# GSM_GPS.net
KiCad netlist of a schematic drawn in EAGLE
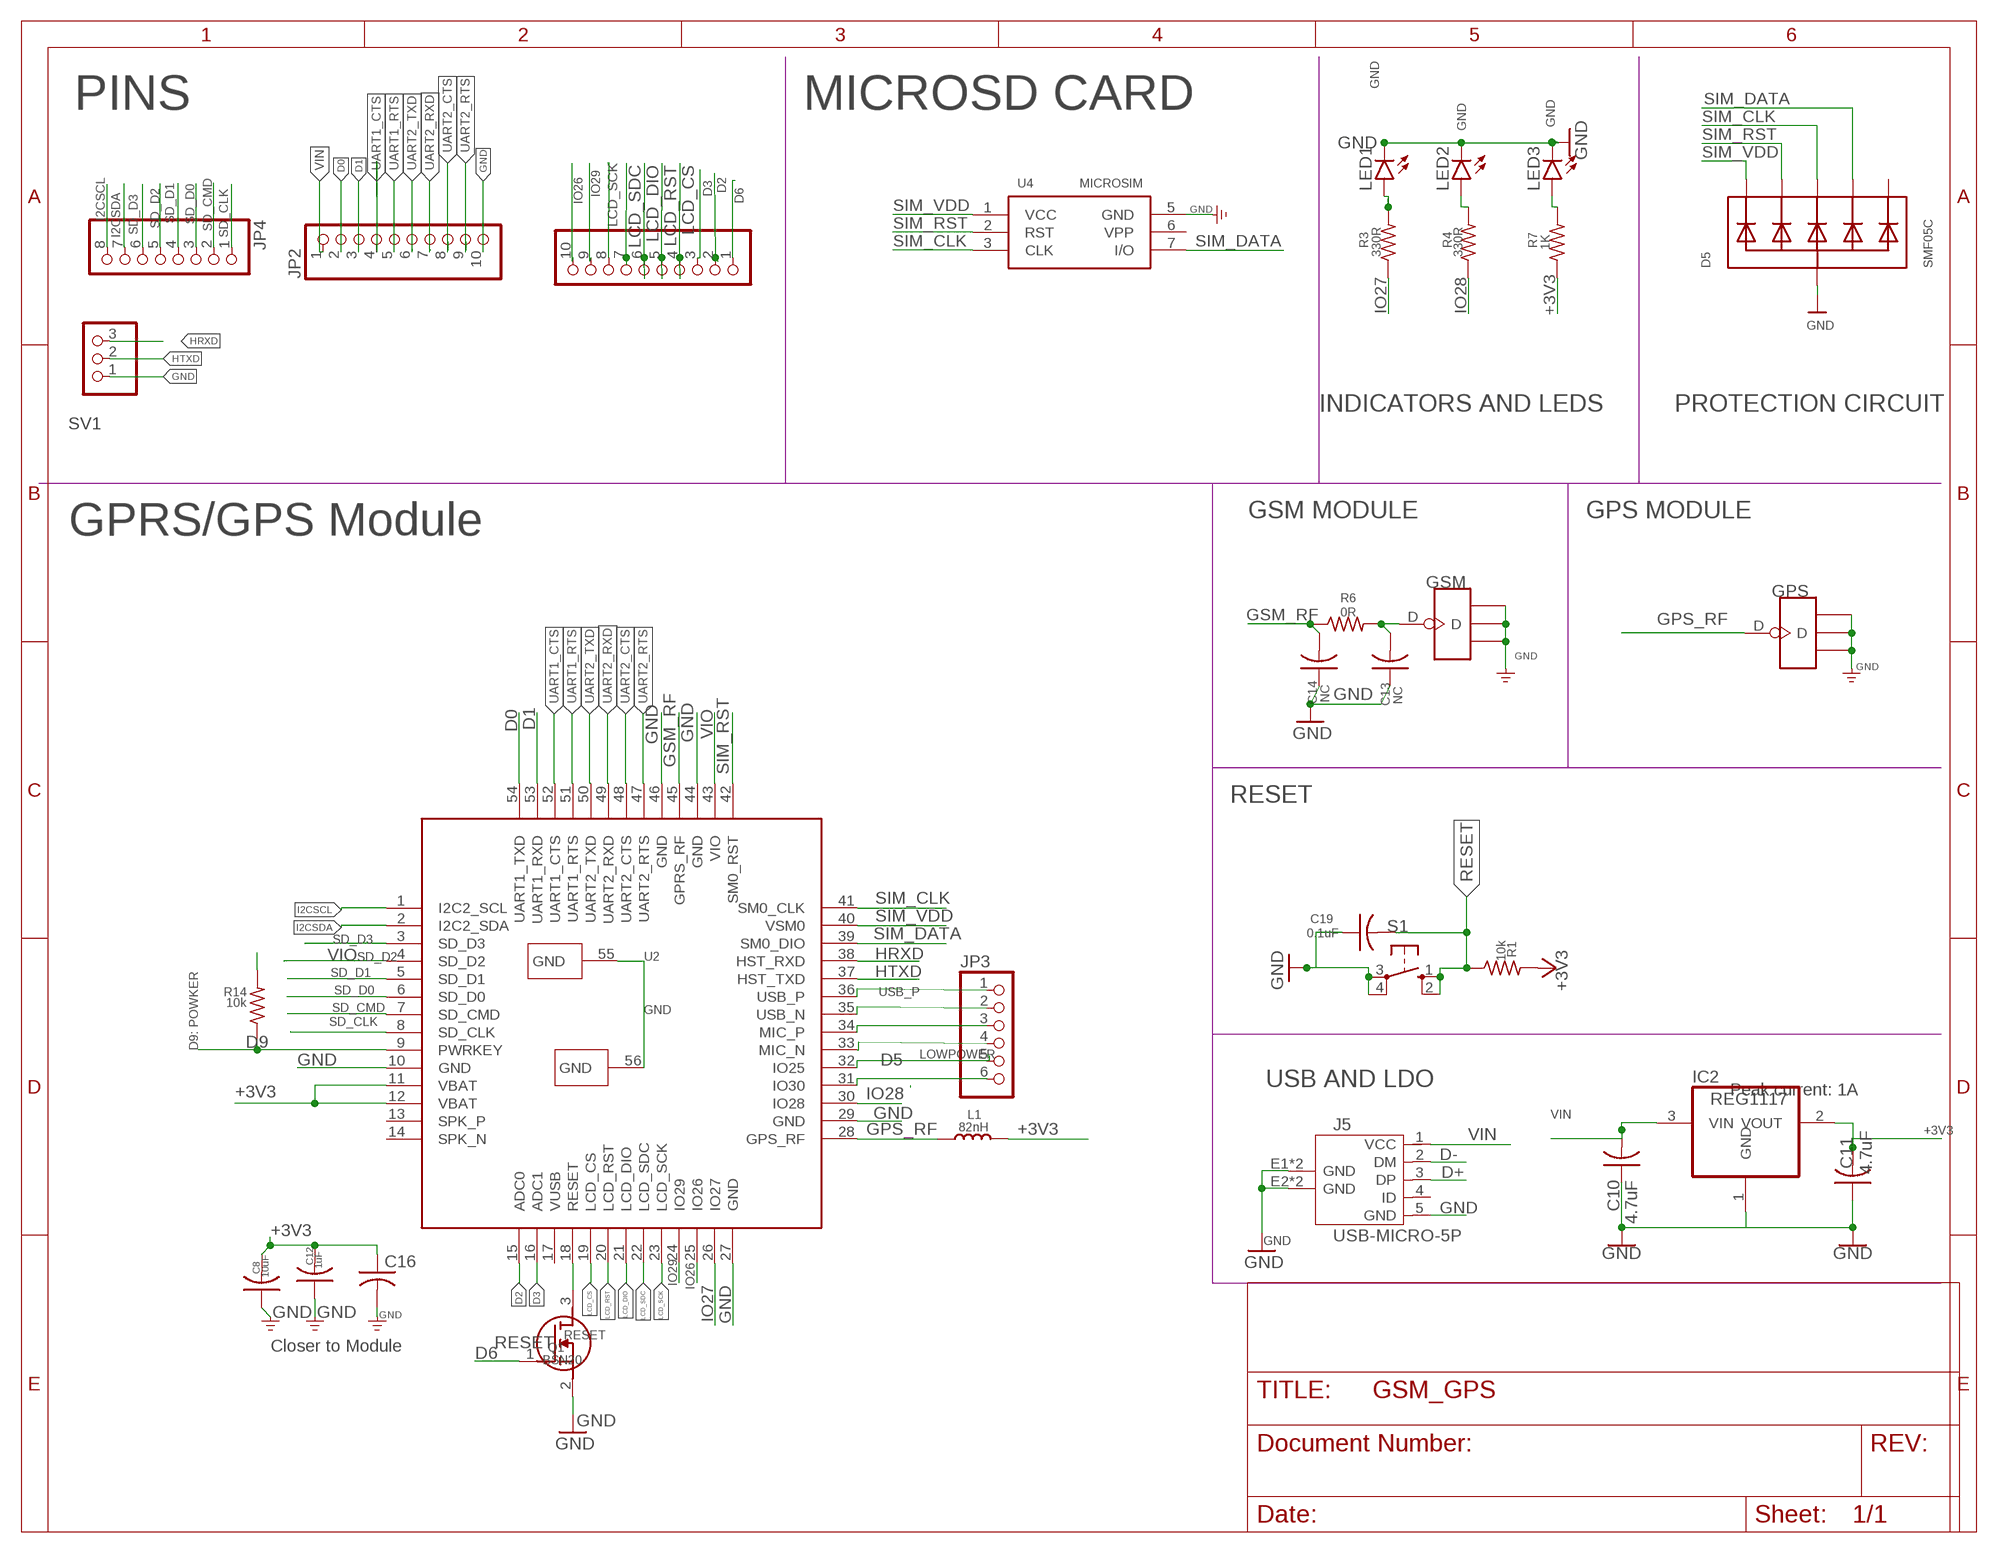
[diagram p0: schematic, sheet 1]

(export (version "E")
  (design (tool "Eeschema 10.0.6"))
  (components
    (comp (ref "C8")
      (value "10uF")
      (footprint "eagle-import:C0805")
      (libsource (lib "eagle-import") (part "C-USC0805"))
    )
    (comp (ref "C10")
      (value "4.7uF")
      (footprint "eagle-import:C0805")
      (libsource (lib "eagle-import") (part "C-USC0805"))
    )
    (comp (ref "C11")
      (value "4.7uF")
      (footprint "eagle-import:C0805")
      (libsource (lib "eagle-import") (part "C-USC0805"))
    )
    (comp (ref "C12")
      (value "1uF")
      (footprint "eagle-import:C0805")
      (libsource (lib "eagle-import") (part "C-USC0805"))
    )
    (comp (ref "C13")
      (value "NC")
      (footprint "eagle-import:C0805")
      (libsource (lib "eagle-import") (part "C-USC0805"))
    )
    (comp (ref "C14")
      (value "NC")
      (footprint "eagle-import:C0805")
      (libsource (lib "eagle-import") (part "C-USC0805"))
    )
    (comp (ref "C16")
      (value "100uF")
      (footprint "eagle-import:C0805")
      (libsource (lib "eagle-import") (part "C-USC0805"))
    )
    (comp (ref "C19")
      (value "0.1uF")
      (footprint "eagle-import:C0805")
      (libsource (lib "eagle-import") (part "C-USC0805"))
    )
    (comp (ref "D5")
      (value "SMF05C")
      (footprint "eagle-import:SOT363")
      (libsource (lib "eagle-import") (part "TVSARRAY_5LANE"))
    )
    (comp (ref "GPS")
      (value "ANTENNA-U-FL")
      (footprint "eagle-import:4P-U-FL")
      (libsource (lib "eagle-import") (part "ANTENNA-U-FL"))
    )
    (comp (ref "GSM")
      (value "ANTENNA-U-FL")
      (footprint "eagle-import:4P-U-FL")
      (libsource (lib "eagle-import") (part "ANTENNA-U-FL"))
    )
    (comp (ref "IC2")
      (value "REG1117")
      (footprint "eagle-import:SOT223")
      (libsource (lib "eagle-import") (part "REG1117"))
    )
    (comp (ref "J2")
      (value "PINHD-1X10")
      (footprint "eagle-import:1X10")
      (libsource (lib "eagle-import") (part "PINHD-1X10"))
    )
    (comp (ref "J5")
      (value "USB-MICRO-5P")
      (footprint "eagle-import:MICRO-USB-5P")
      (libsource (lib "eagle-import") (part "USB-MICRO-5P"))
    )
    (comp (ref "JP2")
      (value "PINHD-1X10")
      (footprint "eagle-import:1X10")
      (libsource (lib "eagle-import") (part "PINHD-1X10"))
    )
    (comp (ref "JP3")
      (value "PINHD-1X6")
      (footprint "eagle-import:1X06")
      (libsource (lib "eagle-import") (part "PINHD-1X6"))
    )
    (comp (ref "JP4")
      (value "PINHD-1X8")
      (footprint "eagle-import:1X08")
      (libsource (lib "eagle-import") (part "PINHD-1X8"))
    )
    (comp (ref "L1")
      (value "82nH")
      (footprint "eagle-import:L0603")
      (libsource (lib "eagle-import") (part "L'0603'"))
    )
    (comp (ref "LED1")
      (value "LEDCHIPLED_0805")
      (footprint "eagle-import:CHIPLED_0805")
      (libsource (lib "eagle-import") (part "LEDCHIPLED_0805"))
    )
    (comp (ref "LED2")
      (value "LEDCHIPLED_0805")
      (footprint "eagle-import:CHIPLED_0805")
      (libsource (lib "eagle-import") (part "LEDCHIPLED_0805"))
    )
    (comp (ref "LED3")
      (value "LEDCHIPLED_0805")
      (footprint "eagle-import:CHIPLED_0805")
      (libsource (lib "eagle-import") (part "LEDCHIPLED_0805"))
    )
    (comp (ref "Q1")
      (value "BSN20")
      (footprint "eagle-import:SOT95P237X112-3N")
      (fields
        (field (name "ARROW_PART_NUMBER") "SI2302CDS-T1-E3")
        (field (name "MOUSER_PART_NUMBER") "781-SI2302CDS-E3")
      )
      (libsource (lib "eagle-import") (part "SI2302CDS-T1-E3"))
    )
    (comp (ref "R1")
      (value "10k")
      (footprint "eagle-import:R0805")
      (libsource (lib "eagle-import") (part "R-US_R0805"))
    )
    (comp (ref "R3")
      (value "330R")
      (footprint "eagle-import:R0805")
      (libsource (lib "eagle-import") (part "R-US_R0805"))
    )
    (comp (ref "R4")
      (value "330R")
      (footprint "eagle-import:R0805")
      (libsource (lib "eagle-import") (part "R-US_R0805"))
    )
    (comp (ref "R6")
      (value "0R")
      (footprint "eagle-import:R0805")
      (libsource (lib "eagle-import") (part "R-US_R0805"))
    )
    (comp (ref "R7")
      (value "1K")
      (footprint "eagle-import:R0805")
      (libsource (lib "eagle-import") (part "R-US_R0805"))
    )
    (comp (ref "R14")
      (value "10k")
      (footprint "eagle-import:R0805")
      (libsource (lib "eagle-import") (part "R-US_R0805"))
    )
    (comp (ref "S1")
      (value "10-XX")
      (footprint "eagle-import:B3F-10XX")
      (fields (field (name "MPN") "B3F-1000"))
      (libsource (lib "eagle-import") (part "10-XX"))
    )
    (comp (ref "SV1")
      (value "PINHD-1X3")
      (footprint "eagle-import:1X03")
      (libsource (lib "eagle-import") (part "PINHD-1X3"))
    )
    (comp (ref "U2")
      (value "A9G")
      (footprint "eagle-import:A9G")
      (libsource (lib "eagle-import") (part "A9G"))
    )
    (comp (ref "U4")
      (value "MICROSIM")
      (footprint "eagle-import:MICROSIM")
      (libsource (lib "eagle-import") (part "MICROSIM"))
    )
  )
  (nets
    (net (code "1") (name "+3V3") (class "Default")
      (node (ref "C11") (pin "2") (pinfunction "2_2") (pintype "passive"))
      (node (ref "C12") (pin "2") (pinfunction "2_2") (pintype "passive"))
      (node (ref "C16") (pin "1") (pinfunction "1_1") (pintype "passive"))
      (node (ref "C8") (pin "2") (pinfunction "2_2") (pintype "passive"))
      (node (ref "IC2") (pin "2") (pinfunction "VOUT_2") (pintype "output"))
      (node (ref "L1") (pin "2") (pinfunction "2_2") (pintype "passive"))
      (node (ref "R1") (pin "2") (pinfunction "2_2") (pintype "passive"))
      (node (ref "R7") (pin "1") (pinfunction "1_1") (pintype "passive"))
      (node (ref "U2") (pin "11") (pinfunction "VBAT_11") (pintype "bidirectional"))
      (node (ref "U2") (pin "12") (pinfunction "VBAT_12") (pintype "bidirectional"))
    )
    (net (code "2") (name "/D+") (class "Default")
      (node (ref "J5") (pin "3") (pinfunction "DP_3") (pintype "bidirectional"))
    )
    (net (code "3") (name "/D-") (class "Default")
      (node (ref "J5") (pin "2") (pinfunction "DM_2") (pintype "bidirectional"))
    )
    (net (code "4") (name "/D5") (class "Default")
      (node (ref "JP3") (pin "5") (pinfunction "5_5") (pintype "passive"))
      (node (ref "U2") (pin "32") (pinfunction "IO25_32") (pintype "bidirectional"))
    )
    (net (code "5") (name "/D6") (class "Default")
      (node (ref "J2") (pin "1") (pinfunction "1_1") (pintype "passive"))
      (node (ref "Q1") (pin "1") (pinfunction "G_1") (pintype "bidirectional"))
    )
    (net (code "6") (name "/D9") (class "Default")
      (node (ref "R14") (pin "1") (pinfunction "1_1") (pintype "passive"))
      (node (ref "U2") (pin "9") (pinfunction "PWRKEY_9") (pintype "bidirectional"))
    )
    (net (code "7") (name "/GPS_RF") (class "Default")
      (node (ref "GPS") (pin "D") (pinfunction "D_D") (pintype "bidirectional"))
      (node (ref "L1") (pin "1") (pinfunction "1_1") (pintype "passive"))
      (node (ref "U2") (pin "28") (pinfunction "GPS_RF_28") (pintype "bidirectional"))
    )
    (net (code "8") (name "/GSM_RF") (class "Default")
      (node (ref "C14") (pin "2") (pinfunction "2_2") (pintype "passive"))
      (node (ref "R6") (pin "1") (pinfunction "1_1") (pintype "passive"))
      (node (ref "U2") (pin "45") (pinfunction "GPRS_RF_45") (pintype "bidirectional"))
    )
    (net (code "9") (name "/IO26") (class "Default")
      (node (ref "J2") (pin "10") (pinfunction "10_10") (pintype "passive"))
      (node (ref "U2") (pin "25") (pinfunction "IO26_25") (pintype "bidirectional"))
    )
    (net (code "10") (name "/IO27") (class "Default")
      (node (ref "R3") (pin "1") (pinfunction "1_1") (pintype "passive"))
      (node (ref "U2") (pin "26") (pinfunction "IO27_26") (pintype "bidirectional"))
    )
    (net (code "11") (name "/IO28") (class "Default")
      (node (ref "R4") (pin "1") (pinfunction "1_1") (pintype "passive"))
      (node (ref "U2") (pin "30") (pinfunction "IO28_30") (pintype "bidirectional"))
    )
    (net (code "12") (name "/IO29") (class "Default")
      (node (ref "J2") (pin "9") (pinfunction "9_9") (pintype "passive"))
      (node (ref "U2") (pin "24") (pinfunction "IO29_24") (pintype "bidirectional"))
    )
    (net (code "13") (name "/SD_CLK") (class "Default")
      (node (ref "JP4") (pin "1") (pinfunction "1_1") (pintype "passive"))
      (node (ref "U2") (pin "8") (pinfunction "SD_CLK_8") (pintype "bidirectional"))
    )
    (net (code "14") (name "/SD_CMD") (class "Default")
      (node (ref "JP4") (pin "2") (pinfunction "2_2") (pintype "passive"))
      (node (ref "U2") (pin "7") (pinfunction "SD_CMD_7") (pintype "bidirectional"))
    )
    (net (code "15") (name "/SD_D0") (class "Default")
      (node (ref "JP4") (pin "3") (pinfunction "3_3") (pintype "passive"))
      (node (ref "U2") (pin "6") (pinfunction "SD_D0_6") (pintype "bidirectional"))
    )
    (net (code "16") (name "/SD_D1") (class "Default")
      (node (ref "JP4") (pin "4") (pinfunction "4_4") (pintype "passive"))
      (node (ref "U2") (pin "5") (pinfunction "SD_D1_5") (pintype "bidirectional"))
    )
    (net (code "17") (name "/SD_D2") (class "Default")
      (node (ref "JP4") (pin "5") (pinfunction "5_5") (pintype "passive"))
      (node (ref "U2") (pin "4") (pinfunction "SD_D2_4") (pintype "bidirectional"))
    )
    (net (code "18") (name "/SD_D3") (class "Default")
      (node (ref "JP4") (pin "6") (pinfunction "6_6") (pintype "passive"))
      (node (ref "U2") (pin "3") (pinfunction "SD_D3_3") (pintype "bidirectional"))
    )
    (net (code "19") (name "/SIM_CLK") (class "Default")
      (node (ref "D5") (pin "4") (pinfunction "C3_4") (pintype "passive"))
      (node (ref "U2") (pin "41") (pinfunction "SM0_CLK_41") (pintype "bidirectional"))
      (node (ref "U4") (pin "3") (pinfunction "CLK_3") (pintype "bidirectional"))
    )
    (net (code "20") (name "/SIM_DATA") (class "Default")
      (node (ref "D5") (pin "5") (pinfunction "C4_5") (pintype "passive"))
      (node (ref "U2") (pin "39") (pinfunction "SM0_DIO_39") (pintype "bidirectional"))
      (node (ref "U4") (pin "7") (pinfunction "I/O_7") (pintype "bidirectional"))
    )
    (net (code "21") (name "/SIM_RST") (class "Default")
      (node (ref "D5") (pin "3") (pinfunction "C2_3") (pintype "passive"))
      (node (ref "U2") (pin "42") (pinfunction "SM0_RST_42") (pintype "bidirectional"))
      (node (ref "U4") (pin "2") (pinfunction "RST_2") (pintype "bidirectional"))
    )
    (net (code "22") (name "/SIM_VDD") (class "Default")
      (node (ref "D5") (pin "1") (pinfunction "C1_1") (pintype "passive"))
      (node (ref "U2") (pin "40") (pinfunction "VSM0_40") (pintype "bidirectional"))
      (node (ref "U4") (pin "1") (pinfunction "VCC_1") (pintype "bidirectional"))
    )
    (net (code "23") (name "/USB_P") (class "Default")
      (node (ref "JP3") (pin "1") (pinfunction "1_1") (pintype "passive"))
      (node (ref "U2") (pin "36") (pinfunction "USB_P_36") (pintype "bidirectional"))
    )
    (net (code "24") (name "/VIO") (class "Default")
      (node (ref "R14") (pin "2") (pinfunction "2_2") (pintype "passive"))
      (node (ref "U2") (pin "43") (pinfunction "VIO_43") (pintype "bidirectional"))
    )
    (net (code "25") (name "D0") (class "Default")
      (node (ref "JP2") (pin "2") (pinfunction "2_2") (pintype "passive"))
      (node (ref "U2") (pin "54") (pinfunction "UART1_TXD_54") (pintype "bidirectional"))
    )
    (net (code "26") (name "D1") (class "Default")
      (node (ref "JP2") (pin "3") (pinfunction "3_3") (pintype "passive"))
      (node (ref "U2") (pin "53") (pinfunction "UART1_RXD_53") (pintype "bidirectional"))
    )
    (net (code "27") (name "D2") (class "Default")
      (node (ref "J2") (pin "2") (pinfunction "2_2") (pintype "passive"))
      (node (ref "U2") (pin "15") (pinfunction "ADC0_15") (pintype "bidirectional"))
    )
    (net (code "28") (name "D3") (class "Default")
      (node (ref "J2") (pin "3") (pinfunction "3_3") (pintype "passive"))
      (node (ref "U2") (pin "16") (pinfunction "ADC1_16") (pintype "bidirectional"))
    )
    (net (code "29") (name "GND") (class "Default")
      (node (ref "C10") (pin "1") (pinfunction "1_1") (pintype "passive"))
      (node (ref "C11") (pin "1") (pinfunction "1_1") (pintype "passive"))
      (node (ref "C12") (pin "1") (pinfunction "1_1") (pintype "passive"))
      (node (ref "C13") (pin "1") (pinfunction "1_1") (pintype "passive"))
      (node (ref "C14") (pin "1") (pinfunction "1_1") (pintype "passive"))
      (node (ref "C16") (pin "2") (pinfunction "2_2") (pintype "passive"))
      (node (ref "C19") (pin "1") (pinfunction "1_1") (pintype "passive"))
      (node (ref "C8") (pin "1") (pinfunction "1_1") (pintype "passive"))
      (node (ref "D5") (pin "2") (pinfunction "A_2") (pintype "passive"))
      (node (ref "GPS") (pin "GND1") (pinfunction "GND1_GND1") (pintype "bidirectional"))
      (node (ref "GPS") (pin "GND2") (pinfunction "GND2_GND2") (pintype "bidirectional"))
      (node (ref "GPS") (pin "GND3") (pinfunction "GND3_GND3") (pintype "bidirectional"))
      (node (ref "GSM") (pin "GND1") (pinfunction "GND1_GND1") (pintype "bidirectional"))
      (node (ref "GSM") (pin "GND2") (pinfunction "GND2_GND2") (pintype "bidirectional"))
      (node (ref "GSM") (pin "GND3") (pinfunction "GND3_GND3") (pintype "bidirectional"))
      (node (ref "IC2") (pin "1") (pinfunction "GND_1") (pintype "power_in"))
      (node (ref "J5") (pin "5") (pinfunction "GND_5") (pintype "bidirectional"))
      (node (ref "J5") (pin "E1") (pinfunction "GND_E1") (pintype "bidirectional"))
      (node (ref "J5") (pin "E2") (pinfunction "GND_E2") (pintype "bidirectional"))
      (node (ref "J5") (pin "P1") (pinfunction "GND_P1") (pintype "bidirectional"))
      (node (ref "J5") (pin "P2") (pinfunction "GND_P2") (pintype "bidirectional"))
      (node (ref "JP2") (pin "10") (pinfunction "10_10") (pintype "passive"))
      (node (ref "LED1") (pin "C") (pinfunction "C_C") (pintype "passive"))
      (node (ref "LED2") (pin "C") (pinfunction "C_C") (pintype "passive"))
      (node (ref "LED3") (pin "C") (pinfunction "C_C") (pintype "passive"))
      (node (ref "Q1") (pin "2") (pinfunction "S_2") (pintype "bidirectional"))
      (node (ref "S1") (pin "3") (pinfunction "P_3") (pintype "passive"))
      (node (ref "S1") (pin "4") (pinfunction "P1_4") (pintype "passive"))
      (node (ref "SV1") (pin "1") (pinfunction "1_1") (pintype "passive"))
      (node (ref "U2") (pin "10") (pinfunction "GND_10") (pintype "bidirectional"))
      (node (ref "U2") (pin "27") (pinfunction "GND_27") (pintype "bidirectional"))
      (node (ref "U2") (pin "29") (pinfunction "GND_29") (pintype "bidirectional"))
      (node (ref "U2") (pin "44") (pinfunction "GND_44") (pintype "bidirectional"))
      (node (ref "U2") (pin "46") (pinfunction "GND_46") (pintype "bidirectional"))
      (node (ref "U2") (pin "55") (pinfunction "GND_55") (pintype "bidirectional"))
      (node (ref "U2") (pin "56") (pinfunction "GND_56") (pintype "bidirectional"))
      (node (ref "U4") (pin "5") (pinfunction "GND_5") (pintype "bidirectional"))
    )
    (net (code "30") (name "HRXD") (class "Default")
      (node (ref "SV1") (pin "3") (pinfunction "3_3") (pintype "passive"))
      (node (ref "U2") (pin "38") (pinfunction "HST_RXD_38") (pintype "bidirectional"))
    )
    (net (code "31") (name "HTXD") (class "Default")
      (node (ref "SV1") (pin "2") (pinfunction "2_2") (pintype "passive"))
      (node (ref "U2") (pin "37") (pinfunction "HST_TXD_37") (pintype "bidirectional"))
    )
    (net (code "32") (name "I2CSCL") (class "Default")
      (node (ref "JP4") (pin "8") (pinfunction "8_8") (pintype "passive"))
      (node (ref "U2") (pin "1") (pinfunction "I2C2_SCL_1") (pintype "bidirectional"))
    )
    (net (code "33") (name "I2CSDA") (class "Default")
      (node (ref "JP4") (pin "7") (pinfunction "7_7") (pintype "passive"))
      (node (ref "U2") (pin "2") (pinfunction "I2C2_SDA_2") (pintype "bidirectional"))
    )
    (net (code "34") (name "LCD_CS") (class "Default")
      (node (ref "J2") (pin "4") (pinfunction "4_4") (pintype "passive"))
      (node (ref "U2") (pin "19") (pinfunction "LCD_CS_19") (pintype "bidirectional"))
    )
    (net (code "35") (name "LCD_DIO") (class "Default")
      (node (ref "J2") (pin "6") (pinfunction "6_6") (pintype "passive"))
      (node (ref "U2") (pin "21") (pinfunction "LCD_DIO_21") (pintype "bidirectional"))
    )
    (net (code "36") (name "LCD_RST") (class "Default")
      (node (ref "J2") (pin "5") (pinfunction "5_5") (pintype "passive"))
      (node (ref "U2") (pin "20") (pinfunction "LCD_RST_20") (pintype "bidirectional"))
    )
    (net (code "37") (name "LCD_SCK") (class "Default")
      (node (ref "J2") (pin "8") (pinfunction "8_8") (pintype "passive"))
      (node (ref "U2") (pin "23") (pinfunction "LCD_SCK_23") (pintype "bidirectional"))
    )
    (net (code "38") (name "LCD_SDC") (class "Default")
      (node (ref "J2") (pin "7") (pinfunction "7_7") (pintype "passive"))
      (node (ref "U2") (pin "22") (pinfunction "LCD_SDC_22") (pintype "bidirectional"))
    )
    (net (code "39") (name "Net-(C13-Pad2)") (class "Default")
      (node (ref "C13") (pin "2") (pinfunction "2_2") (pintype "passive"))
      (node (ref "GSM") (pin "D") (pinfunction "D_D") (pintype "bidirectional"))
      (node (ref "R6") (pin "2") (pinfunction "2_2") (pintype "passive"))
    )
    (net (code "40") (name "Net-(LED1-PadA)") (class "Default")
      (node (ref "LED1") (pin "A") (pinfunction "A_A") (pintype "passive"))
      (node (ref "R3") (pin "2") (pinfunction "2_2") (pintype "passive"))
    )
    (net (code "41") (name "Net-(LED2-PadA)") (class "Default")
      (node (ref "LED2") (pin "A") (pinfunction "A_A") (pintype "passive"))
      (node (ref "R4") (pin "2") (pinfunction "2_2") (pintype "passive"))
    )
    (net (code "42") (name "Net-(LED3-PadA)") (class "Default")
      (node (ref "LED3") (pin "A") (pinfunction "A_A") (pintype "passive"))
      (node (ref "R7") (pin "2") (pinfunction "2_2") (pintype "passive"))
    )
    (net (code "43") (name "Net-(U2-IO30)") (class "Default")
      (node (ref "JP3") (pin "6") (pinfunction "6_6") (pintype "passive"))
      (node (ref "U2") (pin "31") (pinfunction "IO30_31") (pintype "bidirectional"))
    )
    (net (code "44") (name "Net-(U2-MIC_N)") (class "Default")
      (node (ref "JP3") (pin "4") (pinfunction "4_4") (pintype "passive"))
      (node (ref "U2") (pin "33") (pinfunction "MIC_N_33") (pintype "bidirectional"))
    )
    (net (code "45") (name "Net-(U2-MIC_P)") (class "Default")
      (node (ref "JP3") (pin "3") (pinfunction "3_3") (pintype "passive"))
      (node (ref "U2") (pin "34") (pinfunction "MIC_P_34") (pintype "bidirectional"))
    )
    (net (code "46") (name "Net-(U2-USB_N)") (class "Default")
      (node (ref "JP3") (pin "2") (pinfunction "2_2") (pintype "passive"))
      (node (ref "U2") (pin "35") (pinfunction "USB_N_35") (pintype "bidirectional"))
    )
    (net (code "47") (name "RESET") (class "Default")
      (node (ref "C19") (pin "2") (pinfunction "2_2") (pintype "passive"))
      (node (ref "Q1") (pin "3") (pinfunction "D_3") (pintype "bidirectional"))
      (node (ref "R1") (pin "1") (pinfunction "1_1") (pintype "passive"))
      (node (ref "S1") (pin "1") (pinfunction "S_1") (pintype "passive"))
      (node (ref "S1") (pin "2") (pinfunction "S1_2") (pintype "passive"))
      (node (ref "U2") (pin "18") (pinfunction "RESET_18") (pintype "bidirectional"))
    )
    (net (code "48") (name "UART1_CTS") (class "Default")
      (node (ref "JP2") (pin "4") (pinfunction "4_4") (pintype "passive"))
      (node (ref "U2") (pin "52") (pinfunction "UART1_CTS_52") (pintype "bidirectional"))
    )
    (net (code "49") (name "UART1_RTS") (class "Default")
      (node (ref "JP2") (pin "5") (pinfunction "5_5") (pintype "passive"))
      (node (ref "U2") (pin "51") (pinfunction "UART1_RTS_51") (pintype "bidirectional"))
    )
    (net (code "50") (name "UART2_CTS") (class "Default")
      (node (ref "JP2") (pin "8") (pinfunction "8_8") (pintype "passive"))
      (node (ref "U2") (pin "48") (pinfunction "UART2_CTS_48") (pintype "bidirectional"))
    )
    (net (code "51") (name "UART2_RTS") (class "Default")
      (node (ref "JP2") (pin "9") (pinfunction "9_9") (pintype "passive"))
      (node (ref "U2") (pin "47") (pinfunction "UART2_RTS_47") (pintype "bidirectional"))
    )
    (net (code "52") (name "UART2_RXD") (class "Default")
      (node (ref "JP2") (pin "7") (pinfunction "7_7") (pintype "passive"))
      (node (ref "U2") (pin "49") (pinfunction "UART2_RXD_49") (pintype "bidirectional"))
    )
    (net (code "53") (name "UART2_TXD") (class "Default")
      (node (ref "JP2") (pin "6") (pinfunction "6_6") (pintype "passive"))
      (node (ref "U2") (pin "50") (pinfunction "UART2_TXD_50") (pintype "bidirectional"))
    )
    (net (code "54") (name "VIN") (class "Default")
      (node (ref "C10") (pin "2") (pinfunction "2_2") (pintype "passive"))
      (node (ref "IC2") (pin "3") (pinfunction "VIN_3") (pintype "input"))
      (node (ref "J5") (pin "1") (pinfunction "VCC_1") (pintype "bidirectional"))
      (node (ref "JP2") (pin "1") (pinfunction "1_1") (pintype "passive"))
    )
    (net (code "55") (name "unconnected-(D5-C5-Pad6)") (class "Default")
      (node (ref "D5") (pin "6") (pinfunction "C5_6") (pintype "passive"))
    )
    (net (code "56") (name "unconnected-(J5-ID-Pad4)") (class "Default")
      (node (ref "J5") (pin "4") (pinfunction "ID_4") (pintype "bidirectional"))
    )
    (net (code "57") (name "unconnected-(U2-SPK_N-Pad14)") (class "Default")
      (node (ref "U2") (pin "14") (pinfunction "SPK_N_14") (pintype "bidirectional"))
    )
    (net (code "58") (name "unconnected-(U2-SPK_P-Pad13)") (class "Default")
      (node (ref "U2") (pin "13") (pinfunction "SPK_P_13") (pintype "bidirectional"))
    )
    (net (code "59") (name "unconnected-(U2-VUSB-Pad17)") (class "Default")
      (node (ref "U2") (pin "17") (pinfunction "VUSB_17") (pintype "bidirectional"))
    )
    (net (code "60") (name "unconnected-(U4-VPP-Pad6)") (class "Default")
      (node (ref "U4") (pin "6") (pinfunction "VPP_6") (pintype "bidirectional"))
    )
  )
)
